# Power_Supply.net
KiCad netlist of a schematic drawn in Altium Designer
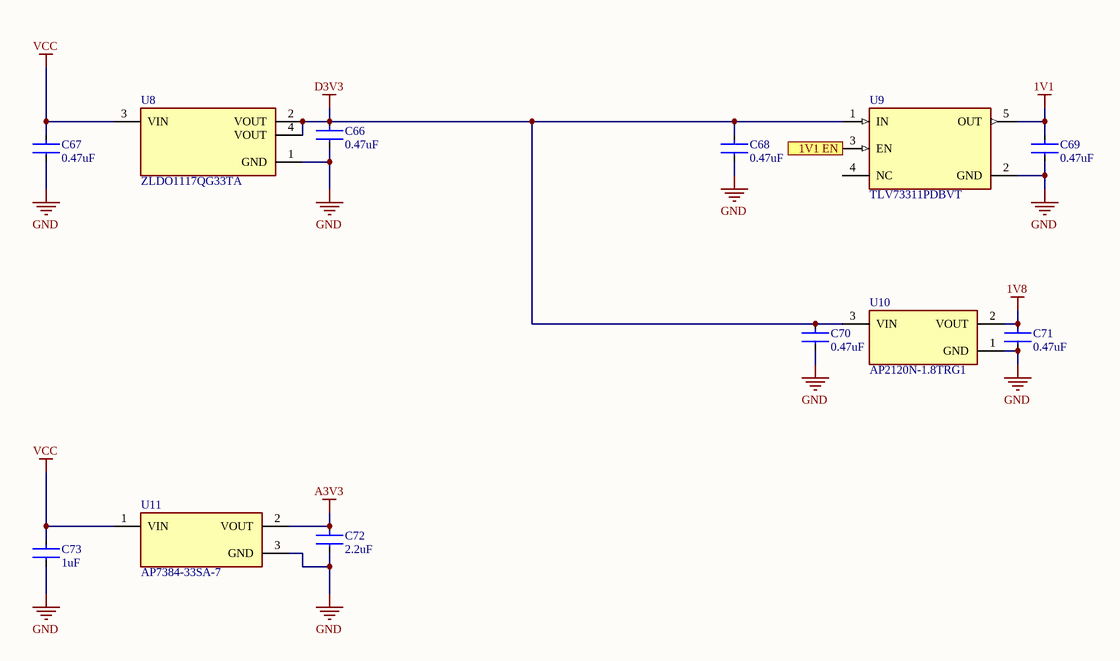
[diagram p0: Power Supply.SchDoc]

(export (version "E")
  (design (tool "Eeschema 10.0.6"))
  (components
    (comp (ref "C66")
      (value "0.47uF")
      (footprint "FP-GRM15-MFG")
      (description "CAP CER 0.1UF 16V X7R 0402")
      (fields (field (name "MANUFACTURER PART NUMBER") "GRM155R71C104KA88D") (field (name "TOLERANCE") "10%"))
      (libsource (lib "Altium Content Vault") (part "236180d848d6139a670b325ea6854c9"))
    )
    (comp (ref "C67")
      (value "0.47uF")
      (footprint "FP-GRM15-MFG")
      (description "CAP CER 0.1UF 16V X7R 0402")
      (fields (field (name "MANUFACTURER PART NUMBER") "GRM155R71C104KA88D") (field (name "TOLERANCE") "10%"))
      (libsource (lib "Altium Content Vault") (part "236180d848d6139a670b325ea6854c9"))
    )
    (comp (ref "C68")
      (value "0.47uF")
      (footprint "FP-GRM15-MFG")
      (description "CAP CER 0.1UF 16V X7R 0402")
      (fields (field (name "MANUFACTURER PART NUMBER") "GRM155R71C104KA88D") (field (name "TOLERANCE") "10%"))
      (libsource (lib "Altium Content Vault") (part "236180d848d6139a670b325ea6854c9"))
    )
    (comp (ref "C69")
      (value "0.47uF")
      (footprint "FP-GRM15-MFG")
      (description "CAP CER 0.1UF 16V X7R 0402")
      (fields (field (name "MANUFACTURER PART NUMBER") "GRM155R71C104KA88D") (field (name "TOLERANCE") "10%"))
      (libsource (lib "Altium Content Vault") (part "236180d848d6139a670b325ea6854c9"))
    )
    (comp (ref "C70")
      (value "0.47uF")
      (footprint "FP-GRM15-MFG")
      (description "CAP CER 0.1UF 16V X7R 0402")
      (fields (field (name "MANUFACTURER PART NUMBER") "GRM155R71C104KA88D") (field (name "TOLERANCE") "10%"))
      (libsource (lib "Altium Content Vault") (part "236180d848d6139a670b325ea6854c9"))
    )
    (comp (ref "C71")
      (value "0.47uF")
      (footprint "FP-GRM15-MFG")
      (description "CAP CER 0.1UF 16V X7R 0402")
      (fields (field (name "MANUFACTURER PART NUMBER") "GRM155R71C104KA88D") (field (name "TOLERANCE") "10%"))
      (libsource (lib "Altium Content Vault") (part "236180d848d6139a670b325ea6854c9"))
    )
    (comp (ref "C72")
      (value "2.2uF")
      (footprint "FP-GRM15-MFG")
      (description "CAP CER 0.1UF 16V X7R 0402")
      (fields (field (name "MANUFACTURER PART NUMBER") "GRM155R71C104KA88D") (field (name "TOLERANCE") "10%"))
      (libsource (lib "Altium Content Vault") (part "236180d848d6139a670b325ea6854c9"))
    )
    (comp (ref "C73")
      (value "1uF")
      (footprint "FP-GRM15-MFG")
      (description "CAP CER 0.1UF 16V X7R 0402")
      (fields (field (name "MANUFACTURER PART NUMBER") "GRM155R71C104KA88D") (field (name "TOLERANCE") "10%"))
      (libsource (lib "Altium Content Vault") (part "236180d848d6139a670b325ea6854c9"))
    )
    (comp (ref "U8")
      (value "ZLDO1117QG33TA")
      (footprint "FP-SOT223-MFG")
      (description "IC REG LINEAR 3.3V 1A SOT223-3")
      (fields (field (name "TOLERANCE") "2%"))
      (libsource (lib "Altium Content Vault") (part "e8e3cda12977690329f4a6520c2f0b2"))
    )
    (comp (ref "U9")
      (value "TLV73311PDBVT")
      (footprint "FP-DBV0005A-IPC_C")
      (description "IC REG LINEAR 1.1V 300MA SOT23-5")
      (libsource (lib "Altium Content Vault") (part "4670bf8a164e1b8604192632250c220"))
    )
    (comp (ref "U10")
      (value "AP2120N-1.8TRG1")
      (footprint "FP-SOT23-IPC_A")
      (description "IC REG LINEAR 1.8V 150MA SOT23")
      (libsource (lib "Altium Content Vault") (part "99960f24aedc7394e144d1df79132fe"))
    )
    (comp (ref "U11")
      (value "AP7384-33SA-7")
      (footprint "FP-SOT23-IPC_A")
      (description "IC REG LIN 3.3V SOT23 T&R 3K")
      (libsource (lib "Altium Content Vault") (part "962e5ce8f08f2276f18e857990e14fe"))
    )
  )
  (nets
    (net (code "1") (name "/1V1 EN") (class "Default")
      (node (ref "U9") (pin "3") (pinfunction "EN_3") (pintype "input"))
    )
    (net (code "2") (name "1V1") (class "Default")
      (node (ref "C69") (pin "2") (pinfunction "2_2") (pintype "passive"))
      (node (ref "U9") (pin "5") (pinfunction "OUT_5") (pintype "output"))
    )
    (net (code "3") (name "1V8") (class "Default")
      (node (ref "C71") (pin "2") (pinfunction "2_2") (pintype "passive"))
      (node (ref "U10") (pin "2") (pinfunction "VOUT_2") (pintype "power_in"))
    )
    (net (code "4") (name "A3V3") (class "Default")
      (node (ref "C72") (pin "2") (pinfunction "2_2") (pintype "passive"))
      (node (ref "U11") (pin "2") (pinfunction "VOUT_2") (pintype "power_in"))
    )
    (net (code "5") (name "D3V3") (class "Default")
      (node (ref "C66") (pin "2") (pinfunction "2_2") (pintype "passive"))
      (node (ref "C68") (pin "2") (pinfunction "2_2") (pintype "passive"))
      (node (ref "C70") (pin "2") (pinfunction "2_2") (pintype "passive"))
      (node (ref "U10") (pin "3") (pinfunction "VIN_3") (pintype "power_in"))
      (node (ref "U8") (pin "2") (pinfunction "VOUT_2") (pintype "power_in"))
      (node (ref "U8") (pin "4") (pinfunction "VOUT_4") (pintype "power_in"))
      (node (ref "U9") (pin "1") (pinfunction "IN_1") (pintype "input"))
    )
    (net (code "6") (name "GND") (class "Default")
      (node (ref "C66") (pin "1") (pinfunction "1_1") (pintype "passive"))
      (node (ref "C67") (pin "1") (pinfunction "1_1") (pintype "passive"))
      (node (ref "C68") (pin "1") (pinfunction "1_1") (pintype "passive"))
      (node (ref "C69") (pin "1") (pinfunction "1_1") (pintype "passive"))
      (node (ref "C70") (pin "1") (pinfunction "1_1") (pintype "passive"))
      (node (ref "C71") (pin "1") (pinfunction "1_1") (pintype "passive"))
      (node (ref "C72") (pin "1") (pinfunction "1_1") (pintype "passive"))
      (node (ref "C73") (pin "1") (pinfunction "1_1") (pintype "passive"))
      (node (ref "U10") (pin "1") (pinfunction "GND_1") (pintype "power_in"))
      (node (ref "U11") (pin "3") (pinfunction "GND_3") (pintype "power_in"))
      (node (ref "U8") (pin "1") (pinfunction "GND_1") (pintype "power_in"))
      (node (ref "U9") (pin "2") (pinfunction "GND_2") (pintype "power_in"))
    )
    (net (code "7") (name "VCC") (class "Default")
      (node (ref "C67") (pin "2") (pinfunction "2_2") (pintype "passive"))
      (node (ref "C73") (pin "2") (pinfunction "2_2") (pintype "passive"))
      (node (ref "U11") (pin "1") (pinfunction "VIN_1") (pintype "power_in"))
      (node (ref "U8") (pin "3") (pinfunction "VIN_3") (pintype "power_in"))
    )
    (net (code "8") (name "unconnected-(U9-NC-Pad4)") (class "Default")
      (node (ref "U9") (pin "4") (pinfunction "NC_4") (pintype "passive"))
    )
  )
)
